# Control_Box_3_0.net
KiCad netlist of a schematic drawn in EAGLE
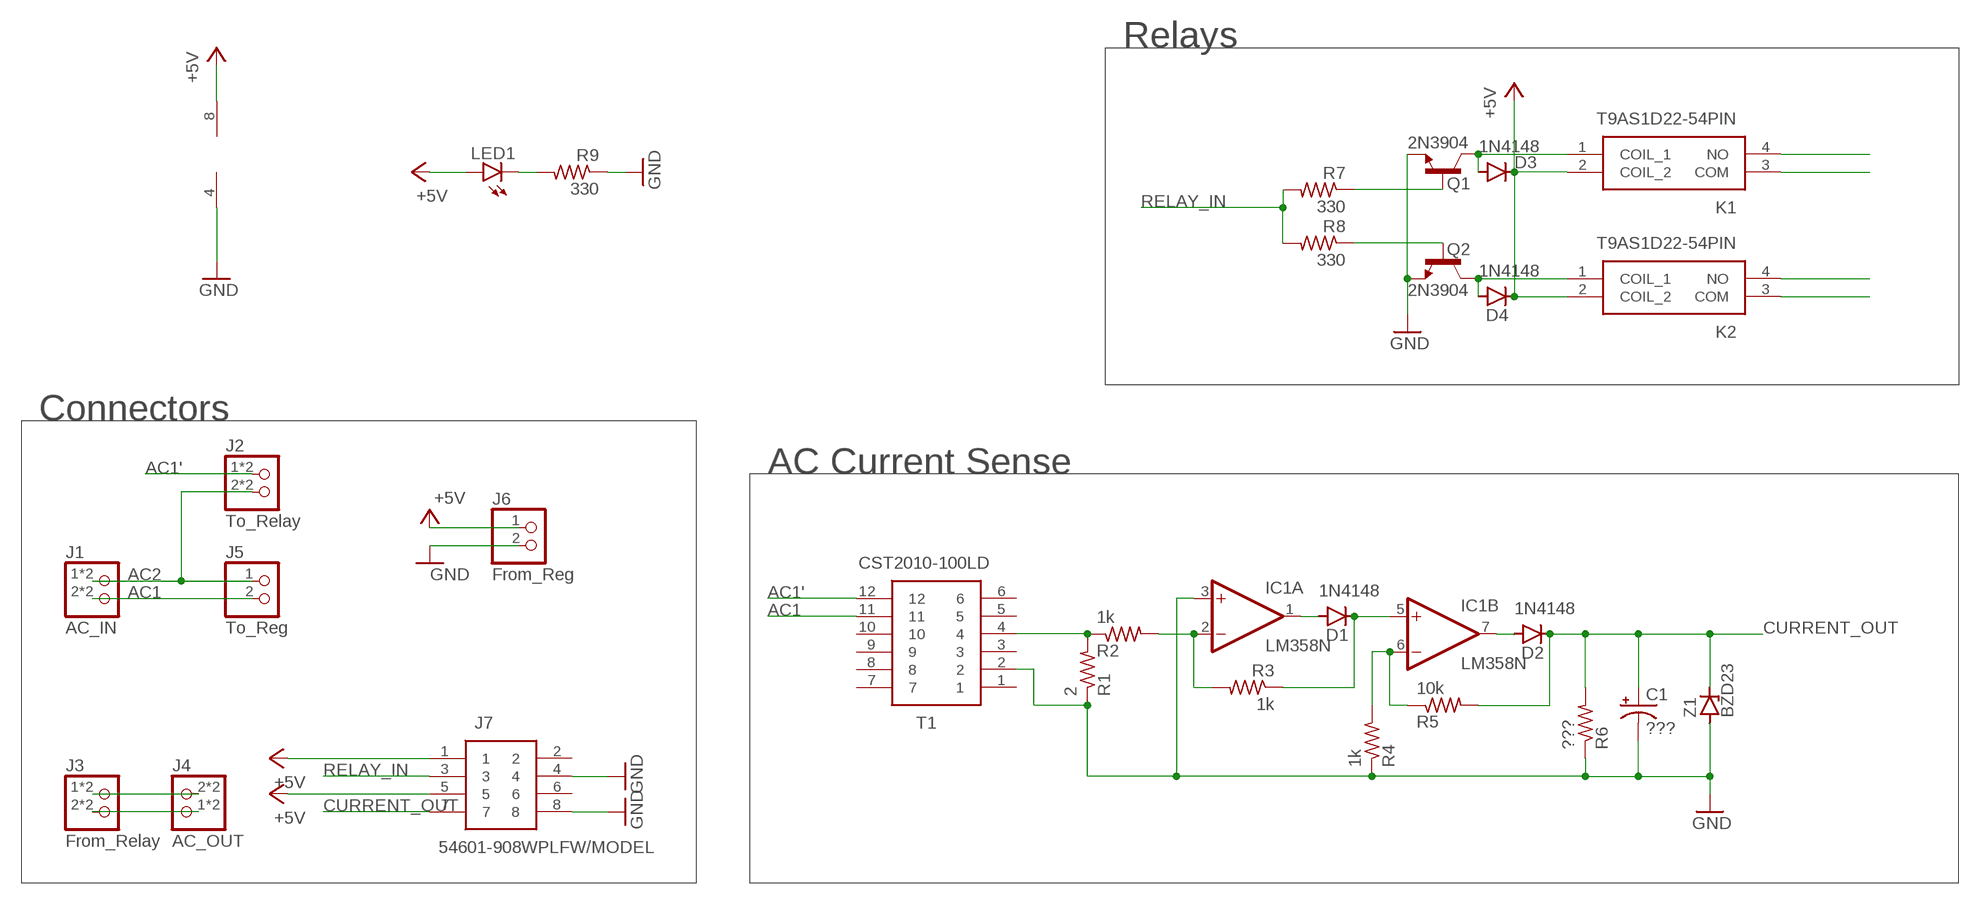
[diagram p0: schematic, sheet 1]

(export (version "E")
  (design (tool "Eeschema 10.0.6"))
  (components
    (comp (ref "C1")
      (value "???")
      (footprint "eagle-import:E1,8-4")
      (libsource (lib "eagle-import") (part "CPOL-USE1.8-4"))
    )
    (comp (ref "D1")
      (value "1N4148")
      (footprint "eagle-import:DO35-7")
      (libsource (lib "eagle-import") (part "1N4148DO35-7"))
    )
    (comp (ref "D2")
      (value "1N4148")
      (footprint "eagle-import:DO35-7")
      (libsource (lib "eagle-import") (part "1N4148DO35-7"))
    )
    (comp (ref "D3")
      (value "1N4148")
      (footprint "eagle-import:DO35-7")
      (libsource (lib "eagle-import") (part "1N4148DO35-7"))
    )
    (comp (ref "D4")
      (value "1N4148")
      (footprint "eagle-import:DO35-7")
      (libsource (lib "eagle-import") (part "1N4148DO35-7"))
    )
    (comp (ref "IC1")
      (value "LM358N")
      (footprint "eagle-import:DIL08")
      (libsource (lib "eagle-import") (part "LM358N"))
    )
    (comp (ref "J1")
      (value "AC_IN")
      (footprint "eagle-import:HDRRA4W64P762_2X2_1016X254X556B")
      (libsource (lib "eagle-import") (part "VC0200500000GVC0200500000G"))
    )
    (comp (ref "J2")
      (value "To_Relay")
      (footprint "eagle-import:HDRRA4W64P762_2X2_1016X254X556B")
      (libsource (lib "eagle-import") (part "VC0200500000GVC0200500000G"))
    )
    (comp (ref "J3")
      (value "From_Relay")
      (footprint "eagle-import:HDRRA4W64P762_2X2_1016X254X556B")
      (libsource (lib "eagle-import") (part "VC0200500000GVC0200500000G"))
    )
    (comp (ref "J4")
      (value "AC_OUT")
      (footprint "eagle-import:HDRRA4W64P762_2X2_1016X254X556B")
      (libsource (lib "eagle-import") (part "VC0200500000GVC0200500000G"))
    )
    (comp (ref "J5")
      (value "To_Reg")
      (footprint "eagle-import:HDRV2W64P792_1X2_1016X508X838B")
      (libsource (lib "eagle-import") (part "VH_1X2GAP"))
    )
    (comp (ref "J6")
      (value "From_Reg")
      (footprint "eagle-import:HDRV2W165P396_1X2_1016X508X838B")
      (libsource (lib "eagle-import") (part "VH_1X2"))
    )
    (comp (ref "J7")
      (value "54601-908WPLFW/MODEL")
      (footprint "eagle-import:HDRV4W64P254_1X4_1016X508X838B")
      (libsource (lib "eagle-import") (part "54601-908WPLFW/MODEL"))
    )
    (comp (ref "K1")
      (value "T9AS1D22-54PIN")
      (footprint "eagle-import:T9AS5D1212313932103-2")
      (libsource (lib "eagle-import") (part "T9AS1D22-54PIN"))
    )
    (comp (ref "K2")
      (value "T9AS1D22-54PIN")
      (footprint "eagle-import:T9AS5D1212313932103-2")
      (libsource (lib "eagle-import") (part "T9AS1D22-54PIN"))
    )
    (comp (ref "LED1")
      (value "LED5MM")
      (footprint "eagle-import:LED5MM")
      (libsource (lib "eagle-import") (part "LED5MM"))
    )
    (comp (ref "Q1")
      (value "2N3904")
      (footprint "eagle-import:TO92")
      (libsource (lib "eagle-import") (part "2N3904"))
    )
    (comp (ref "Q2")
      (value "2N3904")
      (footprint "eagle-import:TO92")
      (libsource (lib "eagle-import") (part "2N3904"))
    )
    (comp (ref "R1")
      (value "2")
      (footprint "eagle-import:0204_7")
      (libsource (lib "eagle-import") (part "R-US"))
    )
    (comp (ref "R2")
      (value "1k")
      (footprint "eagle-import:0204_7")
      (libsource (lib "eagle-import") (part "R-US"))
    )
    (comp (ref "R3")
      (value "1k")
      (footprint "eagle-import:0204_7")
      (libsource (lib "eagle-import") (part "R-US"))
    )
    (comp (ref "R4")
      (value "1k")
      (footprint "eagle-import:0204_7")
      (libsource (lib "eagle-import") (part "R-US"))
    )
    (comp (ref "R5")
      (value "10k")
      (footprint "eagle-import:0204_7")
      (libsource (lib "eagle-import") (part "R-US"))
    )
    (comp (ref "R6")
      (value "???")
      (footprint "eagle-import:0204_7")
      (libsource (lib "eagle-import") (part "R-US"))
    )
    (comp (ref "R7")
      (value "330")
      (footprint "eagle-import:0204_7")
      (libsource (lib "eagle-import") (part "R-US"))
    )
    (comp (ref "R8")
      (value "330")
      (footprint "eagle-import:0204_7")
      (libsource (lib "eagle-import") (part "R-US"))
    )
    (comp (ref "R9")
      (value "330")
      (footprint "eagle-import:0204_7")
      (libsource (lib "eagle-import") (part "R-US"))
    )
    (comp (ref "T1")
      (value "CST2010-100LD")
      (footprint "eagle-import:CST2010100LD")
      (fields (field (name "MOUSER_PART_NUMBER") "994-CST2010-100LD"))
      (libsource (lib "eagle-import") (part "CST2010-100LD"))
    )
    (comp (ref "Z1")
      (value "BZD23")
      (footprint "eagle-import:SOD81")
      (libsource (lib "eagle-import") (part "BZD23"))
    )
  )
  (nets
    (net (code "1") (name "+5V") (class "Default")
      (node (ref "D3") (pin "C") (pinfunction "C_C") (pintype "passive"))
      (node (ref "D4") (pin "C") (pinfunction "C_C") (pintype "passive"))
      (node (ref "IC1") (pin "8") (pinfunction "V+_8") (pintype "power_in"))
      (node (ref "J6") (pin "1") (pinfunction "1_1") (pintype "passive"))
      (node (ref "J7") (pin "1") (pinfunction "1_1") (pintype "bidirectional"))
      (node (ref "J7") (pin "5") (pinfunction "5_5") (pintype "bidirectional"))
      (node (ref "K1") (pin "2") (pinfunction "COIL_2_2") (pintype "bidirectional"))
      (node (ref "K2") (pin "2") (pinfunction "COIL_2_2") (pintype "bidirectional"))
      (node (ref "LED1") (pin "A") (pinfunction "A_A") (pintype "passive"))
    )
    (net (code "2") (name "/AC1") (class "Default")
      (node (ref "J1") (pin "2") (pinfunction "2_2") (pintype "passive"))
      (node (ref "J1") (pin "3") (pinfunction "2_3") (pintype "passive"))
      (node (ref "J5") (pin "2") (pinfunction "2_2") (pintype "passive"))
      (node (ref "T1") (pin "11") (pinfunction "11_11") (pintype "bidirectional"))
    )
    (net (code "3") (name "/AC1'") (class "Default")
      (node (ref "J2") (pin "1") (pinfunction "1_1") (pintype "passive"))
      (node (ref "J2") (pin "4") (pinfunction "1_4") (pintype "passive"))
      (node (ref "T1") (pin "12") (pinfunction "12_12") (pintype "bidirectional"))
    )
    (net (code "4") (name "/AC2") (class "Default")
      (node (ref "J1") (pin "1") (pinfunction "1_1") (pintype "passive"))
      (node (ref "J1") (pin "4") (pinfunction "1_4") (pintype "passive"))
      (node (ref "J2") (pin "2") (pinfunction "2_2") (pintype "passive"))
      (node (ref "J2") (pin "3") (pinfunction "2_3") (pintype "passive"))
      (node (ref "J5") (pin "1") (pinfunction "1_1") (pintype "passive"))
    )
    (net (code "5") (name "/CURRENT_OUT") (class "Default")
      (node (ref "C1") (pin "+") (pinfunction "+_+") (pintype "passive"))
      (node (ref "D2") (pin "C") (pinfunction "C_C") (pintype "passive"))
      (node (ref "J7") (pin "7") (pinfunction "7_7") (pintype "bidirectional"))
      (node (ref "R5") (pin "2") (pinfunction "2_2") (pintype "passive"))
      (node (ref "R6") (pin "2") (pinfunction "2_2") (pintype "passive"))
      (node (ref "Z1") (pin "C") (pinfunction "C_C") (pintype "passive"))
    )
    (net (code "6") (name "/RELAY_IN") (class "Default")
      (node (ref "J7") (pin "3") (pinfunction "3_3") (pintype "bidirectional"))
      (node (ref "R7") (pin "2") (pinfunction "2_2") (pintype "passive"))
      (node (ref "R8") (pin "2") (pinfunction "2_2") (pintype "passive"))
    )
    (net (code "7") (name "GND") (class "Default")
      (node (ref "C1") (pin "-") (pinfunction "-_-") (pintype "passive"))
      (node (ref "IC1") (pin "3") (pinfunction "+IN_3") (pintype "input"))
      (node (ref "IC1") (pin "4") (pinfunction "V-_4") (pintype "power_in"))
      (node (ref "J6") (pin "2") (pinfunction "2_2") (pintype "passive"))
      (node (ref "J7") (pin "4") (pinfunction "4_4") (pintype "bidirectional"))
      (node (ref "J7") (pin "8") (pinfunction "8_8") (pintype "bidirectional"))
      (node (ref "Q1") (pin "3") (pinfunction "E_3") (pintype "passive"))
      (node (ref "Q2") (pin "3") (pinfunction "E_3") (pintype "passive"))
      (node (ref "R1") (pin "1") (pinfunction "1_1") (pintype "passive"))
      (node (ref "R4") (pin "1") (pinfunction "1_1") (pintype "passive"))
      (node (ref "R6") (pin "1") (pinfunction "1_1") (pintype "passive"))
      (node (ref "R9") (pin "1") (pinfunction "1_1") (pintype "passive"))
      (node (ref "T1") (pin "2") (pinfunction "2_2") (pintype "bidirectional"))
      (node (ref "Z1") (pin "A") (pinfunction "A_A") (pintype "passive"))
    )
    (net (code "8") (name "Net-(IC1A--IN)") (class "Default")
      (node (ref "IC1") (pin "2") (pinfunction "-IN_2") (pintype "input"))
      (node (ref "R2") (pin "2") (pinfunction "2_2") (pintype "passive"))
      (node (ref "R3") (pin "2") (pinfunction "2_2") (pintype "passive"))
    )
    (net (code "9") (name "Net-(IC1A-OUT)") (class "Default")
      (node (ref "D1") (pin "A") (pinfunction "A_A") (pintype "passive"))
      (node (ref "IC1") (pin "1") (pinfunction "OUT_1") (pintype "output"))
    )
    (net (code "10") (name "Net-(IC1B-+IN)") (class "Default")
      (node (ref "D1") (pin "C") (pinfunction "C_C") (pintype "passive"))
      (node (ref "IC1") (pin "5") (pinfunction "+IN_5") (pintype "input"))
      (node (ref "R3") (pin "1") (pinfunction "1_1") (pintype "passive"))
    )
    (net (code "11") (name "Net-(IC1B--IN)") (class "Default")
      (node (ref "IC1") (pin "6") (pinfunction "-IN_6") (pintype "input"))
      (node (ref "R4") (pin "2") (pinfunction "2_2") (pintype "passive"))
      (node (ref "R5") (pin "1") (pinfunction "1_1") (pintype "passive"))
    )
    (net (code "12") (name "Net-(IC1B-OUT)") (class "Default")
      (node (ref "D2") (pin "A") (pinfunction "A_A") (pintype "passive"))
      (node (ref "IC1") (pin "7") (pinfunction "OUT_7") (pintype "output"))
    )
    (net (code "13") (name "Net-(J3-1-Pad4)") (class "Default")
      (node (ref "J3") (pin "1") (pinfunction "1_1") (pintype "passive"))
      (node (ref "J3") (pin "4") (pinfunction "1_4") (pintype "passive"))
      (node (ref "J4") (pin "2") (pinfunction "2_2") (pintype "passive"))
      (node (ref "J4") (pin "3") (pinfunction "2_3") (pintype "passive"))
    )
    (net (code "14") (name "Net-(J3-2-Pad3)") (class "Default")
      (node (ref "J3") (pin "2") (pinfunction "2_2") (pintype "passive"))
      (node (ref "J3") (pin "3") (pinfunction "2_3") (pintype "passive"))
      (node (ref "J4") (pin "1") (pinfunction "1_1") (pintype "passive"))
      (node (ref "J4") (pin "4") (pinfunction "1_4") (pintype "passive"))
    )
    (net (code "15") (name "Net-(K1-COIL_1)") (class "Default")
      (node (ref "D3") (pin "A") (pinfunction "A_A") (pintype "passive"))
      (node (ref "K1") (pin "1") (pinfunction "COIL_1_1") (pintype "bidirectional"))
      (node (ref "Q1") (pin "1") (pinfunction "C_1") (pintype "passive"))
    )
    (net (code "16") (name "Net-(K2-COIL_1)") (class "Default")
      (node (ref "D4") (pin "A") (pinfunction "A_A") (pintype "passive"))
      (node (ref "K2") (pin "1") (pinfunction "COIL_1_1") (pintype "bidirectional"))
      (node (ref "Q2") (pin "1") (pinfunction "C_1") (pintype "passive"))
    )
    (net (code "17") (name "Net-(LED1-C)") (class "Default")
      (node (ref "LED1") (pin "K") (pinfunction "C_K") (pintype "passive"))
      (node (ref "R9") (pin "2") (pinfunction "2_2") (pintype "passive"))
    )
    (net (code "18") (name "Net-(Q1-B)") (class "Default")
      (node (ref "Q1") (pin "2") (pinfunction "B_2") (pintype "passive"))
      (node (ref "R7") (pin "1") (pinfunction "1_1") (pintype "passive"))
    )
    (net (code "19") (name "Net-(Q2-B)") (class "Default")
      (node (ref "Q2") (pin "2") (pinfunction "B_2") (pintype "passive"))
      (node (ref "R8") (pin "1") (pinfunction "1_1") (pintype "passive"))
    )
    (net (code "20") (name "Net-(R1-Pad2)") (class "Default")
      (node (ref "R1") (pin "2") (pinfunction "2_2") (pintype "passive"))
      (node (ref "R2") (pin "1") (pinfunction "1_1") (pintype "passive"))
      (node (ref "T1") (pin "4") (pinfunction "4_4") (pintype "bidirectional"))
    )
    (net (code "21") (name "unconnected-(J7-Pad2)") (class "Default")
      (node (ref "J7") (pin "2") (pinfunction "2_2") (pintype "bidirectional"))
    )
    (net (code "22") (name "unconnected-(J7-Pad6)") (class "Default")
      (node (ref "J7") (pin "6") (pinfunction "6_6") (pintype "bidirectional"))
    )
    (net (code "23") (name "unconnected-(K1-COM-Pad3)") (class "Default")
      (node (ref "K1") (pin "3") (pinfunction "COM_3") (pintype "bidirectional"))
    )
    (net (code "24") (name "unconnected-(K1-NO-Pad4)") (class "Default")
      (node (ref "K1") (pin "4") (pinfunction "NO_4") (pintype "bidirectional"))
    )
    (net (code "25") (name "unconnected-(K2-COM-Pad3)") (class "Default")
      (node (ref "K2") (pin "3") (pinfunction "COM_3") (pintype "bidirectional"))
    )
    (net (code "26") (name "unconnected-(K2-NO-Pad4)") (class "Default")
      (node (ref "K2") (pin "4") (pinfunction "NO_4") (pintype "bidirectional"))
    )
    (net (code "27") (name "unconnected-(T1-Pad1)") (class "Default")
      (node (ref "T1") (pin "1") (pinfunction "1_1") (pintype "bidirectional"))
    )
    (net (code "28") (name "unconnected-(T1-Pad3)") (class "Default")
      (node (ref "T1") (pin "3") (pinfunction "3_3") (pintype "bidirectional"))
    )
    (net (code "29") (name "unconnected-(T1-Pad5)") (class "Default")
      (node (ref "T1") (pin "5") (pinfunction "5_5") (pintype "bidirectional"))
    )
    (net (code "30") (name "unconnected-(T1-Pad6)") (class "Default")
      (node (ref "T1") (pin "6") (pinfunction "6_6") (pintype "bidirectional"))
    )
    (net (code "31") (name "unconnected-(T1-Pad7)") (class "Default")
      (node (ref "T1") (pin "7") (pinfunction "7_7") (pintype "bidirectional"))
    )
    (net (code "32") (name "unconnected-(T1-Pad8)") (class "Default")
      (node (ref "T1") (pin "8") (pinfunction "8_8") (pintype "bidirectional"))
    )
    (net (code "33") (name "unconnected-(T1-Pad9)") (class "Default")
      (node (ref "T1") (pin "9") (pinfunction "9_9") (pintype "bidirectional"))
    )
    (net (code "34") (name "unconnected-(T1-Pad10)") (class "Default")
      (node (ref "T1") (pin "10") (pinfunction "10_10") (pintype "bidirectional"))
    )
  )
)
